# working.net
KiCad netlist of a schematic drawn in EAGLE
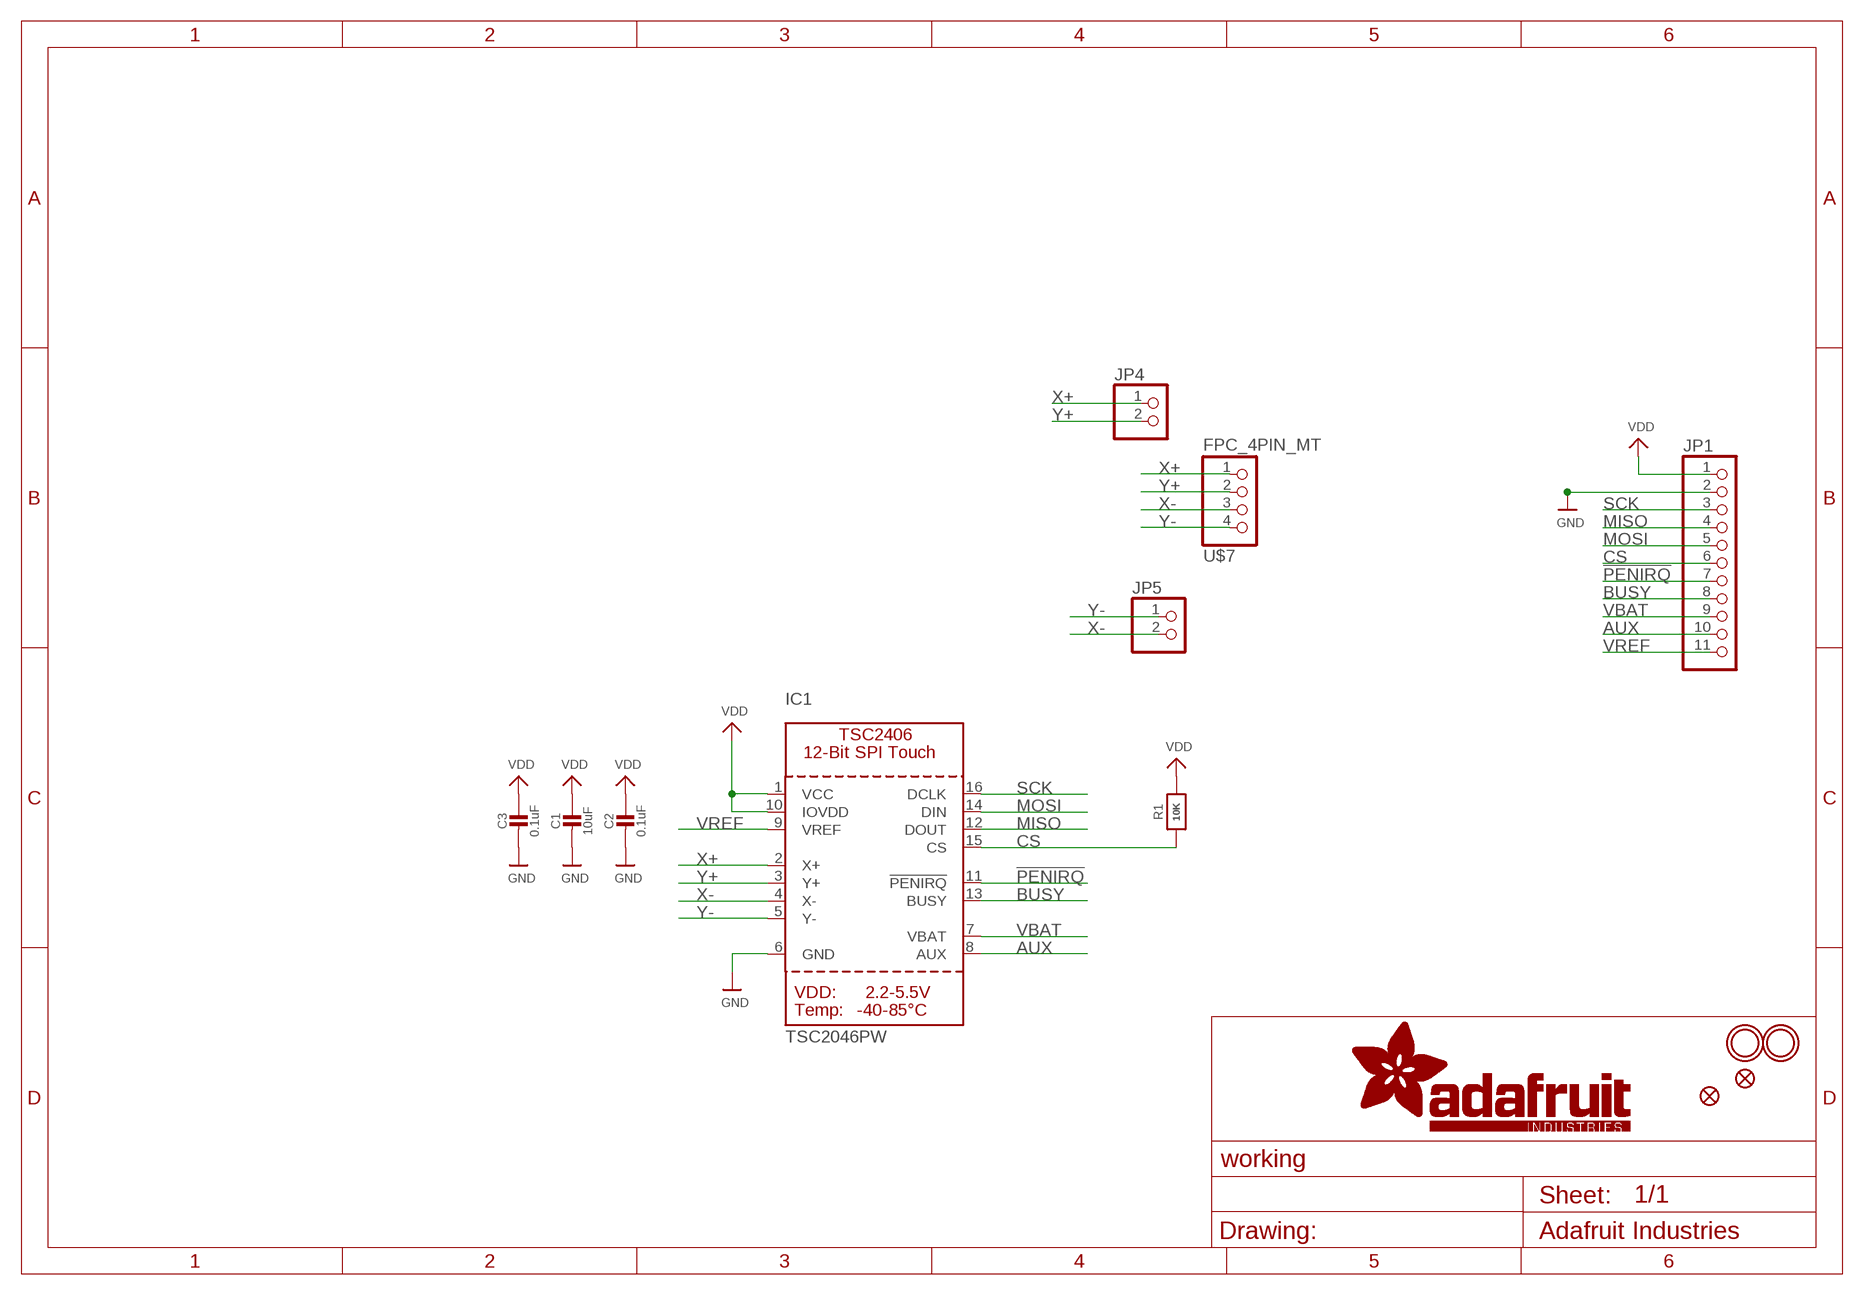
[diagram p0: schematic, sheet 1]

(export (version "E")
  (design (tool "Eeschema 10.0.6"))
  (components
    (comp (ref "C1")
      (value "10uF")
      (footprint "eagle-import:0805-NO")
      (libsource (lib "eagle-import") (part "CAP_CERAMIC0805-NOOUTLINE"))
    )
    (comp (ref "C2")
      (value "0.1uF")
      (footprint "eagle-import:0603-NO")
      (libsource (lib "eagle-import") (part "CAP_CERAMIC0603_NO"))
    )
    (comp (ref "C3")
      (value "0.1uF")
      (footprint "eagle-import:0603-NO")
      (libsource (lib "eagle-import") (part "CAP_CERAMIC0603_NO"))
    )
    (comp (ref "FID2")
      (value "FIDUCIAL_1MM")
      (footprint "eagle-import:FIDUCIAL_1MM")
      (libsource (lib "eagle-import") (part "FIDUCIAL_1MM"))
    )
    (comp (ref "FID3")
      (value "FIDUCIAL_1MM")
      (footprint "eagle-import:FIDUCIAL_1MM")
      (fields (field (name "BOM") "EXCLUDE"))
      (libsource (lib "eagle-import") (part "FIDUCIAL_1MM"))
    )
    (comp (ref "IC1")
      (value "TSC2046PW")
      (footprint "eagle-import:TSSOP16")
      (libsource (lib "eagle-import") (part "TSC2046PW"))
    )
    (comp (ref "JP1")
      (value "HEADER-1X11")
      (footprint "eagle-import:1X11_ROUND")
      (libsource (lib "eagle-import") (part "HEADER-1X11"))
    )
    (comp (ref "JP4")
      (value "HEADER-1X2ROUND")
      (footprint "eagle-import:1X02_ROUND")
      (libsource (lib "eagle-import") (part "HEADER-1X2ROUND"))
    )
    (comp (ref "JP5")
      (value "HEADER-1X2ROUND")
      (footprint "eagle-import:1X02_ROUND")
      (libsource (lib "eagle-import") (part "HEADER-1X2ROUND"))
    )
    (comp (ref "R1")
      (value "10K")
      (footprint "eagle-import:0603-NO")
      (libsource (lib "eagle-import") (part "RESISTOR_0603_NOOUT"))
    )
    (comp (ref "U$4")
      (value "MOUNTINGHOLE2.5")
      (footprint "eagle-import:MOUNTINGHOLE_2.5_PLATED")
      (libsource (lib "eagle-import") (part "MOUNTINGHOLE2.5"))
    )
    (comp (ref "U$5")
      (value "MOUNTINGHOLE2.5")
      (footprint "eagle-import:MOUNTINGHOLE_2.5_PLATED")
      (libsource (lib "eagle-import") (part "MOUNTINGHOLE2.5"))
    )
    (comp (ref "U$7")
      (value "FPC_4PIN_MT")
      (footprint "eagle-import:FPC_CONN_1MM_DUAL_4P_MT")
      (libsource (lib "eagle-import") (part "FPC_4PIN_MT"))
    )
  )
  (nets
    (net (code "1") (name "/AUX") (class "Default")
      (node (ref "IC1") (pin "8") (pinfunction "AUX_8") (pintype "input"))
      (node (ref "JP1") (pin "10") (pinfunction "10_10") (pintype "passive"))
    )
    (net (code "2") (name "/BUSY") (class "Default")
      (node (ref "IC1") (pin "13") (pinfunction "BUSY_13") (pintype "output"))
      (node (ref "JP1") (pin "8") (pinfunction "8_8") (pintype "passive"))
    )
    (net (code "3") (name "/CS") (class "Default")
      (node (ref "IC1") (pin "15") (pinfunction "CS_15") (pintype "input"))
      (node (ref "JP1") (pin "6") (pinfunction "6_6") (pintype "passive"))
      (node (ref "R1") (pin "1") (pinfunction "1_1") (pintype "passive"))
    )
    (net (code "4") (name "/MISO") (class "Default")
      (node (ref "IC1") (pin "12") (pinfunction "DOUT_12") (pintype "output"))
      (node (ref "JP1") (pin "4") (pinfunction "4_4") (pintype "passive"))
    )
    (net (code "5") (name "/MOSI") (class "Default")
      (node (ref "IC1") (pin "14") (pinfunction "DIN_14") (pintype "input"))
      (node (ref "JP1") (pin "5") (pinfunction "5_5") (pintype "passive"))
    )
    (net (code "6") (name "/SCK") (class "Default")
      (node (ref "IC1") (pin "16") (pinfunction "DCLK_16") (pintype "input"))
      (node (ref "JP1") (pin "3") (pinfunction "3_3") (pintype "passive"))
    )
    (net (code "7") (name "/VBAT") (class "Default")
      (node (ref "IC1") (pin "7") (pinfunction "VBAT_7") (pintype "input"))
      (node (ref "JP1") (pin "9") (pinfunction "9_9") (pintype "passive"))
    )
    (net (code "8") (name "/VREF") (class "Default")
      (node (ref "IC1") (pin "9") (pinfunction "VREF_9") (pintype "bidirectional"))
      (node (ref "JP1") (pin "11") (pinfunction "11_11") (pintype "passive"))
    )
    (net (code "9") (name "/X+") (class "Default")
      (node (ref "IC1") (pin "2") (pinfunction "X+_2") (pintype "input"))
      (node (ref "JP4") (pin "1") (pinfunction "1_1") (pintype "passive"))
      (node (ref "U$7") (pin "1") (pinfunction "4_1") (pintype "passive"))
    )
    (net (code "10") (name "/X-") (class "Default")
      (node (ref "IC1") (pin "4") (pinfunction "X-_4") (pintype "input"))
      (node (ref "JP5") (pin "2") (pinfunction "2_2") (pintype "passive"))
      (node (ref "U$7") (pin "3") (pinfunction "2_3") (pintype "passive"))
    )
    (net (code "11") (name "/Y+") (class "Default")
      (node (ref "IC1") (pin "3") (pinfunction "Y+_3") (pintype "input"))
      (node (ref "JP4") (pin "2") (pinfunction "2_2") (pintype "passive"))
      (node (ref "U$7") (pin "2") (pinfunction "3_2") (pintype "passive"))
    )
    (net (code "12") (name "/Y-") (class "Default")
      (node (ref "IC1") (pin "5") (pinfunction "Y-_5") (pintype "input"))
      (node (ref "JP5") (pin "1") (pinfunction "1_1") (pintype "passive"))
      (node (ref "U$7") (pin "4") (pinfunction "1_4") (pintype "passive"))
    )
    (net (code "13") (name "/~{PENIRQ}") (class "Default")
      (node (ref "IC1") (pin "11") (pinfunction "~{PENIRQ}_11") (pintype "output"))
      (node (ref "JP1") (pin "7") (pinfunction "7_7") (pintype "passive"))
    )
    (net (code "14") (name "GND") (class "Default")
      (node (ref "C1") (pin "2") (pinfunction "2_2") (pintype "passive"))
      (node (ref "C2") (pin "2") (pinfunction "2_2") (pintype "passive"))
      (node (ref "C3") (pin "2") (pinfunction "2_2") (pintype "passive"))
      (node (ref "IC1") (pin "6") (pinfunction "GND_6") (pintype "power_in"))
      (node (ref "JP1") (pin "2") (pinfunction "2_2") (pintype "passive"))
    )
    (net (code "15") (name "VDD") (class "Default")
      (node (ref "C1") (pin "1") (pinfunction "1_1") (pintype "passive"))
      (node (ref "C2") (pin "1") (pinfunction "1_1") (pintype "passive"))
      (node (ref "C3") (pin "1") (pinfunction "1_1") (pintype "passive"))
      (node (ref "IC1") (pin "1") (pinfunction "VCC_1") (pintype "power_in"))
      (node (ref "IC1") (pin "10") (pinfunction "IOVDD_10") (pintype "power_in"))
      (node (ref "JP1") (pin "1") (pinfunction "1_1") (pintype "passive"))
      (node (ref "R1") (pin "2") (pinfunction "2_2") (pintype "passive"))
    )
  )
)
